# Schematic.net
KiCad netlist of a schematic drawn in Altium Designer
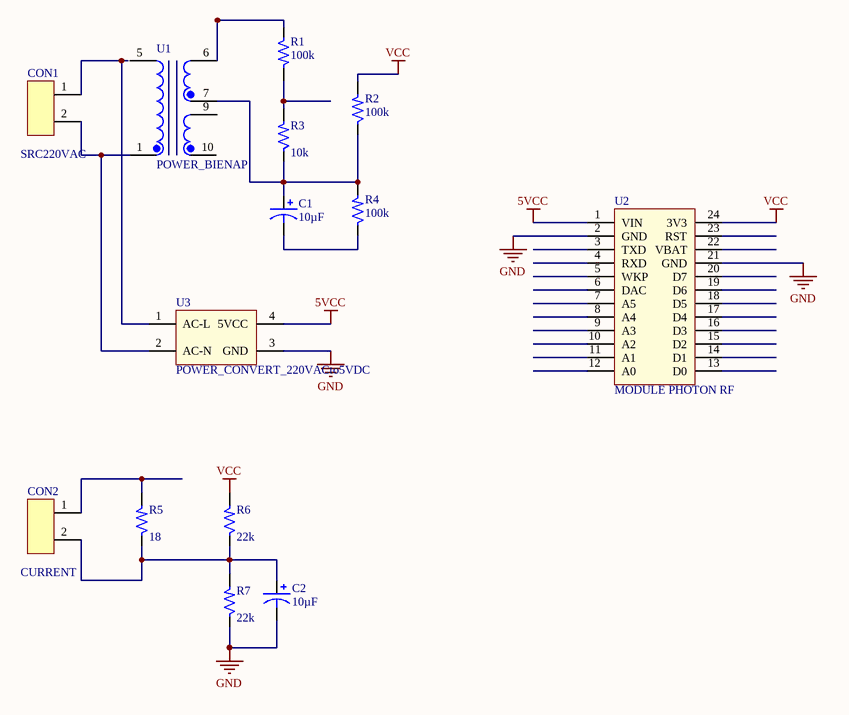
[diagram p0: Schematic.SchDoc]

(export (version "E")
  (design (tool "Eeschema 10.0.6"))
  (components
    (comp (ref "C1")
      (value "C_10uF_HOLE_ALUM_25V")
      (description "CAP ALUM 10uF 20% 25V")
      (fields
        (field (name "MANUFACTURER") "Panasonic Electronic Components")
        (field (name "MANUFACTURER PART NUMBER") "ECE-A1EN100U")
        (field (name "CAPACITANCE") "10µF")
      )
      (libsource (lib "ALTIUM_LIB") (part "C_10uF_HOLE_ALUM_25V"))
    )
    (comp (ref "C2")
      (value "C_10uF_HOLE_ALUM_25V")
      (description "CAP ALUM 10uF 20% 25V")
      (fields
        (field (name "MANUFACTURER") "Panasonic Electronic Components")
        (field (name "MANUFACTURER PART NUMBER") "ECE-A1EN100U")
        (field (name "CAPACITANCE") "10µF")
      )
      (libsource (lib "ALTIUM_LIB") (part "C_10uF_HOLE_ALUM_25V"))
    )
    (comp (ref "CON1")
      (value "SRC220VAC")
      (description "TERM BLOCK HDR 2POS R/A 5.08MM")
      (fields
        (field (name "MANUFACTURER") "TE Connectivity AMP Connectors")
        (field (name "MANUFACTURER PART NUMBER") "282815-2")
      )
      (libsource (lib "ALTIUM_LIB") (part "CON_HEADER_MALE_PIN2"))
    )
    (comp (ref "CON2")
      (value "CURRENT")
      (description "TERM BLOCK HDR 2POS R/A 5.08MM")
      (fields
        (field (name "MANUFACTURER") "TE Connectivity AMP Connectors")
        (field (name "MANUFACTURER PART NUMBER") "282815-2")
      )
      (libsource (lib "ALTIUM_LIB") (part "CON_HEADER_MALE_PIN2"))
    )
    (comp (ref "R1")
      (value "R_100k_HOLE_0.1%_1W")
      (footprint "R_HOLE_0.25W_0.4")
      (description "RESISTOR METAL FILM 1W 100K OHM")
      (fields
        (field (name "MANUFACTURER") "Vishay Dale")
        (field (name "MANUFACTURER PART NUMBER") "CPF1100K00BHEE6")
        (field (name "RESISTANCE (OHMS)") "100k")
      )
      (libsource (lib "ALTIUM_LIB") (part "R_100k_HOLE_0.1%_1W"))
    )
    (comp (ref "R2")
      (value "R_100k_HOLE_0.1%_1W")
      (footprint "R_HOLE_0.25W_0.4")
      (description "RESISTOR METAL FILM 1W 100K OHM")
      (fields
        (field (name "MANUFACTURER") "Vishay Dale")
        (field (name "MANUFACTURER PART NUMBER") "CPF1100K00BHEE6")
        (field (name "RESISTANCE (OHMS)") "100k")
      )
      (libsource (lib "ALTIUM_LIB") (part "R_100k_HOLE_0.1%_1W"))
    )
    (comp (ref "R3")
      (value "R_10K_HOLE_1%_1W")
      (footprint "R_HOLE_0.25W_0.4")
      (description "RES 10.0K OHM 1W 1% AXIAL")
      (fields
        (field (name "MANUFACTURER") "Vishay Dale")
        (field (name "MANUFACTURER PART NUMBER") "CMF6010K000FKEB")
        (field (name "RESISTANCE (OHMS)") "10k")
      )
      (libsource (lib "ALTIUM_LIB") (part "R_10K_HOLE_1%_1W"))
    )
    (comp (ref "R4")
      (value "R_100k_HOLE_0.1%_1W")
      (footprint "R_HOLE_0.25W_0.4")
      (description "RESISTOR METAL FILM 1W 100K OHM")
      (fields
        (field (name "MANUFACTURER") "Vishay Dale")
        (field (name "MANUFACTURER PART NUMBER") "CPF1100K00BHEE6")
        (field (name "RESISTANCE (OHMS)") "100k")
      )
      (libsource (lib "ALTIUM_LIB") (part "R_100k_HOLE_0.1%_1W"))
    )
    (comp (ref "R5")
      (value "R_18_HOLE_1%_1W")
      (footprint "R_HOLE_0.25W_0.4")
      (description "RES 18 OHM 1W 1% AXIAL")
      (fields
        (field (name "MANUFACTURER") "Vishay Dale")
        (field (name "MANUFACTURER PART NUMBER") "ALSR0118R00FE12")
        (field (name "RESISTANCE (OHMS)") "18")
      )
      (libsource (lib "ALTIUM_LIB") (part "R_18_HOLE_1%_1W"))
    )
    (comp (ref "R6")
      (value "R_22K_HOLE_1%_1/4W")
      (footprint "R_HOLE_0.25W_0.4")
      (description "RES 22K OHM 1/4W 1% AXIAL")
      (fields
        (field (name "MANUFACTURER") "Stackpole Electronics Inc.")
        (field (name "MANUFACTURER PART NUMBER") "RNMF14FTC22K0")
        (field (name "RESISTANCE (OHMS)") "22k")
      )
      (libsource (lib "ALTIUM_LIB") (part "R_22K_HOLE_1%_1/4W"))
    )
    (comp (ref "R7")
      (value "R_22K_HOLE_1%_1/4W")
      (footprint "R_HOLE_0.25W_0.4")
      (description "RES 22K OHM 1/4W 1% AXIAL")
      (fields
        (field (name "MANUFACTURER") "Stackpole Electronics Inc.")
        (field (name "MANUFACTURER PART NUMBER") "RNMF14FTC22K0")
        (field (name "RESISTANCE (OHMS)") "22k")
      )
      (libsource (lib "ALTIUM_LIB") (part "R_22K_HOLE_1%_1/4W"))
    )
    (comp (ref "U1")
      (value "POWER_BIENAP")
      (footprint "POWER_BIEN_AP")
      (libsource (lib "ALTIUM_LIB") (part "POWER_BIENAP"))
    )
    (comp (ref "U2")
      (value "MODULE PHOTON RF")
      (footprint "MODULE PHOTON RF")
      (description "PARTICLE PHOTON")
      (fields
        (field (name "MANUFACTURER") "Seeed Technology Co., Ltd")
        (field (name "MANUFACTURER PART NUMBER") "114990286")
      )
      (libsource (lib "ALTIUM_LIB") (part "MODULE PHOTON RF"))
    )
    (comp (ref "U3")
      (value "POWER_CONVERT_220VACto5VDC")
      (footprint "POWER_CONVERT220VACto5VDC")
      (libsource (lib "SchematicLib") (part "POWER_CONVERT_220VACto5VDC"))
    )
  )
  (nets
    (net (code "1") (name "5VCC") (class "Default")
      (node (ref "U2") (pin "1") (pinfunction "VIN_1") (pintype "passive"))
      (node (ref "U3") (pin "4") (pinfunction "5VCC_4") (pintype "passive"))
    )
    (net (code "2") (name "GND") (class "Default")
      (node (ref "C2") (pin "2") (pinfunction "2_2") (pintype "passive"))
      (node (ref "R7") (pin "1") (pinfunction "1_1") (pintype "passive"))
      (node (ref "U2") (pin "2") (pinfunction "GND_2") (pintype "passive"))
      (node (ref "U2") (pin "21") (pinfunction "GND_21") (pintype "passive"))
      (node (ref "U3") (pin "3") (pinfunction "GND_3") (pintype "passive"))
    )
    (net (code "3") (name "Net-(C1-Pad1)") (class "Default")
      (node (ref "C1") (pin "1") (pinfunction "1_1") (pintype "passive"))
      (node (ref "R2") (pin "1") (pinfunction "1_1") (pintype "passive"))
      (node (ref "R3") (pin "1") (pinfunction "1_1") (pintype "passive"))
      (node (ref "R4") (pin "2") (pinfunction "2_2") (pintype "passive"))
      (node (ref "U1") (pin "7") (pinfunction "7_7") (pintype "passive"))
    )
    (net (code "4") (name "Net-(C1-Pad2)") (class "Default")
      (node (ref "C1") (pin "2") (pinfunction "2_2") (pintype "passive"))
      (node (ref "R4") (pin "1") (pinfunction "1_1") (pintype "passive"))
    )
    (net (code "5") (name "Net-(C2-Pad1)") (class "Default")
      (node (ref "C2") (pin "1") (pinfunction "1_1") (pintype "passive"))
      (node (ref "R5") (pin "1") (pinfunction "1_1") (pintype "passive"))
      (node (ref "R6") (pin "1") (pinfunction "1_1") (pintype "passive"))
      (node (ref "R7") (pin "2") (pinfunction "2_2") (pintype "passive"))
    )
    (net (code "6") (name "Net-(R1-Pad1)") (class "Default")
      (node (ref "R1") (pin "1") (pinfunction "1_1") (pintype "passive"))
      (node (ref "U1") (pin "6") (pinfunction "6_6") (pintype "passive"))
    )
    (net (code "7") (name "Net-(R1-Pad2)") (class "Default")
      (node (ref "R1") (pin "2") (pinfunction "2_2") (pintype "passive"))
      (node (ref "R3") (pin "2") (pinfunction "2_2") (pintype "passive"))
    )
    (net (code "8") (name "Net-(U3-AC-N)") (class "Default")
      (node (ref "U1") (pin "1") (pinfunction "1_1") (pintype "passive"))
      (node (ref "U3") (pin "2") (pinfunction "AC-N_2") (pintype "passive"))
    )
    (net (code "9") (name "VCC") (class "Default")
      (node (ref "R2") (pin "2") (pinfunction "2_2") (pintype "passive"))
      (node (ref "R6") (pin "2") (pinfunction "2_2") (pintype "passive"))
      (node (ref "U2") (pin "24") (pinfunction "3V3_24") (pintype "passive"))
    )
    (net (code "10") (name "unconnected-(CON1-SIGN+-Pad1)") (class "Default")
      (node (ref "CON1") (pin "1") (pinfunction "SIGN+_1") (pintype "passive"))
    )
    (net (code "11") (name "unconnected-(CON1-SIGN--Pad2)") (class "Default")
      (node (ref "CON1") (pin "2") (pinfunction "SIGN-_2") (pintype "passive"))
    )
    (net (code "12") (name "unconnected-(CON2-SIGN+-Pad1)") (class "Default")
      (node (ref "CON2") (pin "1") (pinfunction "SIGN+_1") (pintype "passive"))
    )
    (net (code "13") (name "unconnected-(CON2-SIGN--Pad2)") (class "Default")
      (node (ref "CON2") (pin "2") (pinfunction "SIGN-_2") (pintype "passive"))
    )
    (net (code "14") (name "unconnected-(R5-Pad2)") (class "Default")
      (node (ref "R5") (pin "2") (pinfunction "2_2") (pintype "passive"))
    )
    (net (code "15") (name "unconnected-(U1-Pad5)") (class "Default")
      (node (ref "U1") (pin "5") (pinfunction "5_5") (pintype "passive"))
    )
    (net (code "16") (name "unconnected-(U1-Pad9)") (class "Default")
      (node (ref "U1") (pin "9") (pinfunction "9_9") (pintype "passive"))
    )
    (net (code "17") (name "unconnected-(U1-Pad10)") (class "Default")
      (node (ref "U1") (pin "10") (pinfunction "10_10") (pintype "passive"))
    )
    (net (code "18") (name "unconnected-(U2-A0-Pad12)") (class "Default")
      (node (ref "U2") (pin "12") (pinfunction "A0_12") (pintype "passive"))
    )
    (net (code "19") (name "unconnected-(U2-A1-Pad11)") (class "Default")
      (node (ref "U2") (pin "11") (pinfunction "A1_11") (pintype "passive"))
    )
    (net (code "20") (name "unconnected-(U2-A2-Pad10)") (class "Default")
      (node (ref "U2") (pin "10") (pinfunction "A2_10") (pintype "passive"))
    )
    (net (code "21") (name "unconnected-(U2-A3-Pad9)") (class "Default")
      (node (ref "U2") (pin "9") (pinfunction "A3_9") (pintype "passive"))
    )
    (net (code "22") (name "unconnected-(U2-A4-Pad8)") (class "Default")
      (node (ref "U2") (pin "8") (pinfunction "A4_8") (pintype "passive"))
    )
    (net (code "23") (name "unconnected-(U2-A5-Pad7)") (class "Default")
      (node (ref "U2") (pin "7") (pinfunction "A5_7") (pintype "passive"))
    )
    (net (code "24") (name "unconnected-(U2-D0-Pad13)") (class "Default")
      (node (ref "U2") (pin "13") (pinfunction "D0_13") (pintype "passive"))
    )
    (net (code "25") (name "unconnected-(U2-D1-Pad14)") (class "Default")
      (node (ref "U2") (pin "14") (pinfunction "D1_14") (pintype "passive"))
    )
    (net (code "26") (name "unconnected-(U2-D2-Pad15)") (class "Default")
      (node (ref "U2") (pin "15") (pinfunction "D2_15") (pintype "passive"))
    )
    (net (code "27") (name "unconnected-(U2-D3-Pad16)") (class "Default")
      (node (ref "U2") (pin "16") (pinfunction "D3_16") (pintype "passive"))
    )
    (net (code "28") (name "unconnected-(U2-D4-Pad17)") (class "Default")
      (node (ref "U2") (pin "17") (pinfunction "D4_17") (pintype "passive"))
    )
    (net (code "29") (name "unconnected-(U2-D5-Pad18)") (class "Default")
      (node (ref "U2") (pin "18") (pinfunction "D5_18") (pintype "passive"))
    )
    (net (code "30") (name "unconnected-(U2-D6-Pad19)") (class "Default")
      (node (ref "U2") (pin "19") (pinfunction "D6_19") (pintype "passive"))
    )
    (net (code "31") (name "unconnected-(U2-D7-Pad20)") (class "Default")
      (node (ref "U2") (pin "20") (pinfunction "D7_20") (pintype "passive"))
    )
    (net (code "32") (name "unconnected-(U2-DAC-Pad6)") (class "Default")
      (node (ref "U2") (pin "6") (pinfunction "DAC_6") (pintype "passive"))
    )
    (net (code "33") (name "unconnected-(U2-RST-Pad23)") (class "Default")
      (node (ref "U2") (pin "23") (pinfunction "RST_23") (pintype "passive"))
    )
    (net (code "34") (name "unconnected-(U2-RXD-Pad4)") (class "Default")
      (node (ref "U2") (pin "4") (pinfunction "RXD_4") (pintype "passive"))
    )
    (net (code "35") (name "unconnected-(U2-TXD-Pad3)") (class "Default")
      (node (ref "U2") (pin "3") (pinfunction "TXD_3") (pintype "passive"))
    )
    (net (code "36") (name "unconnected-(U2-VBAT-Pad22)") (class "Default")
      (node (ref "U2") (pin "22") (pinfunction "VBAT_22") (pintype "passive"))
    )
    (net (code "37") (name "unconnected-(U2-WKP-Pad5)") (class "Default")
      (node (ref "U2") (pin "5") (pinfunction "WKP_5") (pintype "passive"))
    )
    (net (code "38") (name "unconnected-(U3-AC-L-Pad1)") (class "Default")
      (node (ref "U3") (pin "1") (pinfunction "AC-L_1") (pintype "passive"))
    )
  )
)
